# PCB-3__SCH_PHOENIX.net
KiCad netlist of a schematic drawn in EasyEDA
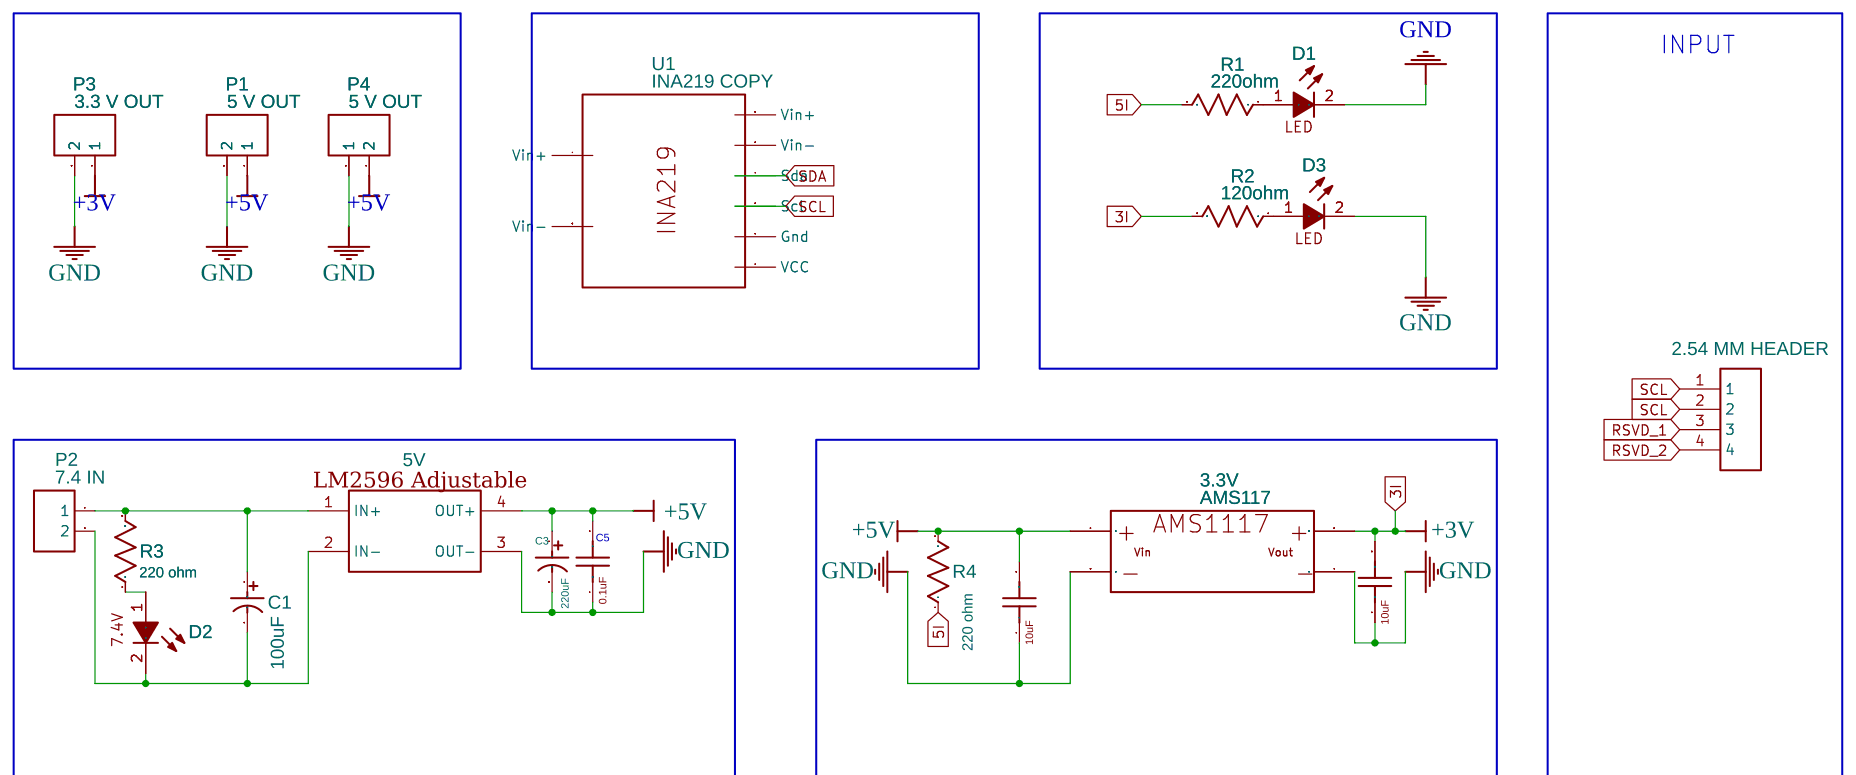
[diagram p0: schematic sheet]

(export (version "E")
  (design (tool "Eeschema 10.0.6"))
  (components
    (comp (ref "3.3V") (value "AMS117") (libsource (lib "") (part "AMS117")))
    (comp (ref "5V") (value "LM2596 ADJ COPY") (libsource (lib "") (part "BuckConverters_LM2596_Adj")))
    (comp (ref "C1")
      (value "100uF")
      (fields
        (field (name "Manufacturer Part") "KM476M016D11RR0VH2FP0")
        (field (name "Manufacturer") "CX(承兴)")
      )
      (libsource (lib "") (part "capacitor 680uF"))
    )
    (comp (ref "C2") (value "22PF CERAMIC CAPACITOR") (libsource (lib "") (part "22PF CERAMIC CAPACITOR")))
    (comp (ref "C3")
      (value "220uF")
      (fields
        (field (name "Manufacturer Part") "KM476M016D11RR0VH2FP0")
        (field (name "Manufacturer") "CX(承兴)")
      )
      (libsource (lib "") (part "capacitor 680uF"))
    )
    (comp (ref "C4") (value "22PF CERAMIC CAPACITOR") (libsource (lib "") (part "22PF CERAMIC CAPACITOR_1")))
    (comp (ref "C5") (value "22PF CERAMIC CAPACITOR") (libsource (lib "") (part "22PF CERAMIC CAPACITOR")))
    (comp (ref "D1")
      (value "LED")
      (fields (field (name "Manufacturer Part") "5600") (field (name "Manufacturer") "VccLite"))
      (libsource (lib "") (part "LED"))
    )
    (comp (ref "D2")
      (value "LED")
      (fields (field (name "Manufacturer Part") "5600") (field (name "Manufacturer") "VccLite"))
      (libsource (lib "") (part "LED_1"))
    )
    (comp (ref "D3")
      (value "LED")
      (fields (field (name "Manufacturer Part") "5600") (field (name "Manufacturer") "VccLite"))
      (libsource (lib "") (part "LED"))
    )
    (comp (ref "H1")
      (value "2.54 MM HEADER")
      (fields (field (name "Manufacturer Part") "2211S-04G") (field (name "Manufacturer") "MULTICOMP PRO"))
      (libsource (lib "") (part "B2B 2.54 MM HEADER"))
    )
    (comp (ref "P1") (value "5 V OUT") (libsource (lib "") (part "CONN-TH_2P-P5.00_2")))
    (comp (ref "P2") (value "7.4 IN") (libsource (lib "") (part "CONN-TH_2P-P5.00")))
    (comp (ref "P3") (value "3.3 V OUT") (libsource (lib "") (part "CONN-TH_2P-P5.00_2")))
    (comp (ref "P4") (value "5 V OUT") (libsource (lib "") (part "CONN-TH_2P-P5.00_1")))
    (comp (ref "R1") (value "220ohm") (libsource (lib "") (part "R_0603_US_1")))
    (comp (ref "R2") (value "120ohm") (libsource (lib "") (part "R_0603_US_1")))
    (comp (ref "R3") (value "220 ohm") (libsource (lib "") (part "R_0603_US")))
    (comp (ref "R4") (value "220 ohm") (libsource (lib "") (part "R_0603_US")))
    (comp (ref "U1")
      (value "INA219 COPY")
      (fields (field (name "Manufacturer Part") "INA219"))
      (libsource (lib "") (part "INA219 COPY"))
    )
  )
  (nets
    (net (code "1") (name "+5V") (class "Default")
      (node (ref "3.3V") (pin "1") (pinfunction "1_1") (pintype "unspecified"))
      (node (ref "5V") (pin "4") (pinfunction "OUT+_4") (pintype "unspecified"))
      (node (ref "C2") (pin "2") (pinfunction "2_2") (pintype "unspecified"))
      (node (ref "C3") (pin "1") (pinfunction "1_1") (pintype "unspecified"))
      (node (ref "C4") (pin "2") (pinfunction "2_2") (pintype "unspecified"))
      (node (ref "P1") (pin "1") (pinfunction "1_1") (pintype "unspecified"))
      (node (ref "P4") (pin "1") (pinfunction "2_1") (pintype "unspecified"))
      (node (ref "R4") (pin "2") (pinfunction "2_2") (pintype "unspecified"))
    )
    (net (code "2") (name "3I") (class "Default")
      (node (ref "3.3V") (pin "3") (pinfunction "3_3") (pintype "unspecified"))
      (node (ref "C5") (pin "2") (pinfunction "2_2") (pintype "unspecified"))
      (node (ref "P3") (pin "1") (pinfunction "1_1") (pintype "unspecified"))
      (node (ref "R2") (pin "2") (pinfunction "2_2") (pintype "unspecified"))
    )
    (net (code "3") (name "5I") (class "Default")
      (node (ref "R1") (pin "2") (pinfunction "2_2") (pintype "unspecified"))
      (node (ref "R4") (pin "1") (pinfunction "1_1") (pintype "unspecified"))
    )
    (net (code "4") (name "GND") (class "Default")
      (node (ref "3.3V") (pin "2") (pinfunction "2_2") (pintype "unspecified"))
      (node (ref "3.3V") (pin "4") (pinfunction "4_4") (pintype "unspecified"))
      (node (ref "5V") (pin "3") (pinfunction "OUT-_3") (pintype "unspecified"))
      (node (ref "C2") (pin "1") (pinfunction "1_1") (pintype "unspecified"))
      (node (ref "C3") (pin "2") (pinfunction "2_2") (pintype "unspecified"))
      (node (ref "C4") (pin "1") (pinfunction "1_1") (pintype "unspecified"))
      (node (ref "C5") (pin "1") (pinfunction "1_1") (pintype "unspecified"))
      (node (ref "D1") (pin "2") (pinfunction "K_2") (pintype "unspecified"))
      (node (ref "D3") (pin "2") (pinfunction "K_2") (pintype "unspecified"))
      (node (ref "P1") (pin "2") (pinfunction "2_2") (pintype "unspecified"))
      (node (ref "P3") (pin "2") (pinfunction "2_2") (pintype "unspecified"))
      (node (ref "P4") (pin "2") (pinfunction "1_2") (pintype "unspecified"))
    )
    (net (code "5") (name "Net-(5V-IN+)") (class "Default")
      (node (ref "5V") (pin "1") (pinfunction "IN+_1") (pintype "unspecified"))
      (node (ref "C1") (pin "1") (pinfunction "1_1") (pintype "unspecified"))
      (node (ref "P2") (pin "1") (pinfunction "1_1") (pintype "unspecified"))
      (node (ref "R3") (pin "2") (pinfunction "2_2") (pintype "unspecified"))
    )
    (net (code "6") (name "Net-(5V-IN-)") (class "Default")
      (node (ref "5V") (pin "2") (pinfunction "IN-_2") (pintype "unspecified"))
      (node (ref "C1") (pin "2") (pinfunction "2_2") (pintype "unspecified"))
      (node (ref "D2") (pin "2") (pinfunction "K_2") (pintype "unspecified"))
      (node (ref "P2") (pin "2") (pinfunction "2_2") (pintype "unspecified"))
    )
    (net (code "7") (name "Net-(D1-A)") (class "Default")
      (node (ref "D1") (pin "1") (pinfunction "A_1") (pintype "unspecified"))
      (node (ref "R1") (pin "1") (pinfunction "1_1") (pintype "unspecified"))
    )
    (net (code "8") (name "Net-(D2-A)") (class "Default")
      (node (ref "D2") (pin "1") (pinfunction "A_1") (pintype "unspecified"))
      (node (ref "R3") (pin "1") (pinfunction "1_1") (pintype "unspecified"))
    )
    (net (code "9") (name "Net-(D3-A)") (class "Default")
      (node (ref "D3") (pin "1") (pinfunction "A_1") (pintype "unspecified"))
      (node (ref "R2") (pin "1") (pinfunction "1_1") (pintype "unspecified"))
    )
    (net (code "10") (name "RSVD_1") (class "Default")
      (node (ref "H1") (pin "3") (pinfunction "3_3") (pintype "unspecified"))
    )
    (net (code "11") (name "RSVD_2") (class "Default")
      (node (ref "H1") (pin "4") (pinfunction "4_4") (pintype "unspecified"))
    )
    (net (code "12") (name "SCL") (class "Default")
      (node (ref "H1") (pin "1") (pinfunction "1_1") (pintype "unspecified"))
      (node (ref "H1") (pin "2") (pinfunction "2_2") (pintype "unspecified"))
      (node (ref "U1") (pin "3") (pinfunction "Scl_3") (pintype "unspecified"))
    )
    (net (code "13") (name "SDA") (class "Default")
      (node (ref "U1") (pin "4") (pinfunction "Sda_4") (pintype "unspecified"))
    )
    (net (code "14") (name "unconnected-(U1-Gnd-Pad2)") (class "Default")
      (node (ref "U1") (pin "2") (pinfunction "Gnd_2") (pintype "unspecified"))
    )
    (net (code "15") (name "unconnected-(U1-VCC-Pad1)") (class "Default")
      (node (ref "U1") (pin "1") (pinfunction "VCC_1") (pintype "unspecified"))
    )
    (net (code "16") (name "unconnected-(U1-Vin+-Pad6)") (class "Default")
      (node (ref "U1") (pin "6") (pinfunction "Vin+_6") (pintype "unspecified"))
    )
    (net (code "17") (name "unconnected-(U1-Vin+-Pad7)") (class "Default")
      (node (ref "U1") (pin "7") (pinfunction "Vin+_7") (pintype "unspecified"))
    )
    (net (code "18") (name "unconnected-(U1-Vin--Pad5)") (class "Default")
      (node (ref "U1") (pin "5") (pinfunction "Vin-_5") (pintype "unspecified"))
    )
    (net (code "19") (name "unconnected-(U1-Vin--Pad8)") (class "Default")
      (node (ref "U1") (pin "8") (pinfunction "Vin-_8") (pintype "unspecified"))
    )
  )
)
